# thermokoppel.net
KiCad netlist of a schematic drawn in Altium Designer
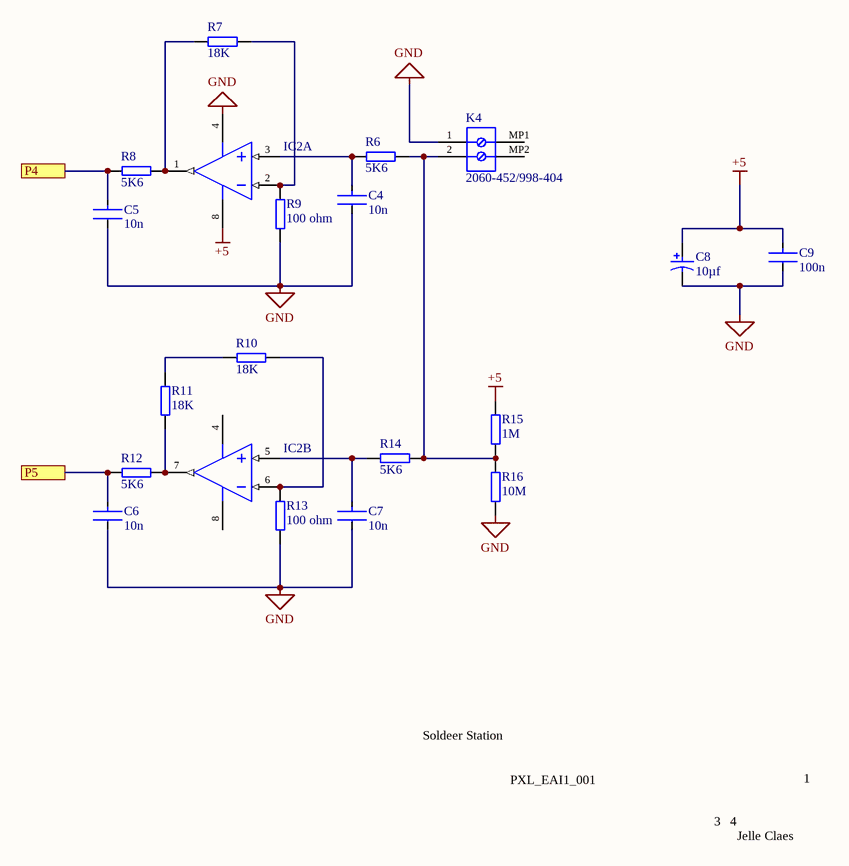
[diagram p0: thermokoppel.SchDoc]

(export (version "E")
  (design (tool "Eeschema 10.0.6"))
  (components
    (comp (ref "C4")
      (value "10n")
      (footprint "CC_0805_m")
      (fields
        (field (name "MANUFACTURER") "KEMET")
        (field (name "OCTOPART") "https://octopart.com/c0805c224k5ractu-kemet-144670")
        (field (name "MANUFACTURER PART NUMBER") "C0805C224K5RACTU")
      )
      (libsource (lib "soldeerstation") (part "Capacitor_Ceramic"))
    )
    (comp (ref "C5")
      (value "10n")
      (footprint "CC_0805_m")
      (fields
        (field (name "MANUFACTURER") "KEMET")
        (field (name "OCTOPART") "https://octopart.com/c0805c224k5ractu-kemet-144670")
        (field (name "MANUFACTURER PART NUMBER") "C0805C224K5RACTU")
      )
      (libsource (lib "soldeerstation") (part "Capacitor_Ceramic"))
    )
    (comp (ref "C6")
      (value "10n")
      (footprint "CC_0805_m")
      (fields
        (field (name "MANUFACTURER") "KEMET")
        (field (name "OCTOPART") "https://octopart.com/c0805c224k5ractu-kemet-144670")
        (field (name "MANUFACTURER PART NUMBER") "C0805C224K5RACTU")
      )
      (libsource (lib "soldeerstation") (part "Capacitor_Ceramic"))
    )
    (comp (ref "C7")
      (value "10n")
      (footprint "CC_0805_m")
      (fields
        (field (name "MANUFACTURER") "KEMET")
        (field (name "OCTOPART") "https://octopart.com/c0805c224k5ractu-kemet-144670")
        (field (name "MANUFACTURER PART NUMBER") "C0805C224K5RACTU")
      )
      (libsource (lib "soldeerstation") (part "Capacitor_Ceramic"))
    )
    (comp (ref "C8")
      (value "10µf")
      (footprint "CE_D8_L10")
      (fields (field (name "MANUFACTURER") "Panasonic"))
      (libsource (lib "soldeerstation") (part "Capacitor_Electrolytic"))
    )
    (comp (ref "C9")
      (value "100n")
      (footprint "CC_0805_m")
      (fields
        (field (name "MANUFACTURER") "KEMET")
        (field (name "OCTOPART") "https://octopart.com/c0805c224k5ractu-kemet-144670")
        (field (name "MANUFACTURER PART NUMBER") "C0805C224K5RACTU")
      )
      (libsource (lib "soldeerstation") (part "Capacitor_Ceramic"))
    )
    (comp (ref "IC2")
      (value "Dual_Opamp")
      (footprint "MSOP_8_M")
      (libsource (lib "soldeerstation") (part "Dual_Opamp"))
    )
    (comp (ref "K4")
      (value "2060-452/998-404")
      (footprint "WAGO-2060-452_V")
      (description "Terminal Block, Pitch 4 mm, 1 x 2 Position, Height 4.5 mm, -60 to 105 degC, RoHS, Tape and Reel")
      (fields (field (name "MANUFACTURER") "WAGO"))
      (libsource (lib "soldeerstation") (part "WAGO-2060"))
    )
    (comp (ref "R6")
      (value "5K6")
      (footprint "R_0805_M")
      (fields (field (name "MANUFACTURER") "Vishay Dale") (field (name "PART NUMBER") "CRCW08050000Z0EA"))
      (libsource (lib "soldeerstation") (part "Resistor"))
    )
    (comp (ref "R7")
      (value "18K")
      (footprint "R_0805_M")
      (fields (field (name "MANUFACTURER") "Vishay Dale") (field (name "PART NUMBER") "CRCW08050000Z0EA"))
      (libsource (lib "soldeerstation") (part "Resistor"))
    )
    (comp (ref "R8")
      (value "5K6")
      (footprint "R_0805_M")
      (fields (field (name "MANUFACTURER") "Vishay Dale") (field (name "PART NUMBER") "CRCW08050000Z0EA"))
      (libsource (lib "soldeerstation") (part "Resistor"))
    )
    (comp (ref "R9")
      (value "100 ohm")
      (footprint "R_0805_M")
      (fields (field (name "MANUFACTURER") "Vishay Dale") (field (name "PART NUMBER") "CRCW08050000Z0EA"))
      (libsource (lib "soldeerstation") (part "Resistor"))
    )
    (comp (ref "R10")
      (value "18K")
      (footprint "R_0805_M")
      (fields (field (name "MANUFACTURER") "Vishay Dale") (field (name "PART NUMBER") "CRCW08050000Z0EA"))
      (libsource (lib "soldeerstation") (part "Resistor"))
    )
    (comp (ref "R11")
      (value "18K")
      (footprint "R_0805_M")
      (fields (field (name "MANUFACTURER") "Vishay Dale") (field (name "PART NUMBER") "CRCW08050000Z0EA"))
      (libsource (lib "soldeerstation") (part "Resistor"))
    )
    (comp (ref "R12")
      (value "5K6")
      (footprint "R_0805_M")
      (fields (field (name "MANUFACTURER") "Vishay Dale") (field (name "PART NUMBER") "CRCW08050000Z0EA"))
      (libsource (lib "soldeerstation") (part "Resistor"))
    )
    (comp (ref "R13")
      (value "100 ohm")
      (footprint "R_0805_M")
      (fields (field (name "MANUFACTURER") "Vishay Dale") (field (name "PART NUMBER") "CRCW08050000Z0EA"))
      (libsource (lib "soldeerstation") (part "Resistor"))
    )
    (comp (ref "R14")
      (value "5K6")
      (footprint "R_0805_M")
      (fields (field (name "MANUFACTURER") "Vishay Dale") (field (name "PART NUMBER") "CRCW08050000Z0EA"))
      (libsource (lib "soldeerstation") (part "Resistor"))
    )
    (comp (ref "R15")
      (value "1M")
      (footprint "R_0805_M")
      (fields (field (name "MANUFACTURER") "Vishay Dale") (field (name "PART NUMBER") "CRCW08050000Z0EA"))
      (libsource (lib "soldeerstation") (part "Resistor"))
    )
    (comp (ref "R16")
      (value "10M")
      (footprint "R_0805_M")
      (fields (field (name "MANUFACTURER") "Vishay Dale") (field (name "PART NUMBER") "CRCW08050000Z0EA"))
      (libsource (lib "soldeerstation") (part "Resistor"))
    )
  )
  (nets
    (net (code "1") (name "+5") (class "Default")
      (node (ref "C8") (pin "2") (pinfunction "2_2") (pintype "passive"))
      (node (ref "C9") (pin "1") (pinfunction "1_1") (pintype "passive"))
      (node (ref "IC2") (pin "8") (pinfunction "VDD_8") (pintype "power_in"))
      (node (ref "R15") (pin "2") (pinfunction "2_2") (pintype "passive"))
    )
    (net (code "2") (name "/P4") (class "Default")
      (node (ref "C5") (pin "1") (pinfunction "1_1") (pintype "passive"))
      (node (ref "R8") (pin "1") (pinfunction "1_1") (pintype "passive"))
    )
    (net (code "3") (name "/P5") (class "Default")
      (node (ref "C6") (pin "1") (pinfunction "1_1") (pintype "passive"))
      (node (ref "R12") (pin "2") (pinfunction "2_2") (pintype "passive"))
    )
    (net (code "4") (name "GND") (class "Default")
      (node (ref "C4") (pin "2") (pinfunction "2_2") (pintype "passive"))
      (node (ref "C5") (pin "2") (pinfunction "2_2") (pintype "passive"))
      (node (ref "C6") (pin "2") (pinfunction "2_2") (pintype "passive"))
      (node (ref "C7") (pin "2") (pinfunction "2_2") (pintype "passive"))
      (node (ref "C8") (pin "1") (pinfunction "1_1") (pintype "passive"))
      (node (ref "C9") (pin "2") (pinfunction "2_2") (pintype "passive"))
      (node (ref "IC2") (pin "4") (pinfunction "VSS_4") (pintype "power_in"))
      (node (ref "K4") (pin "1") (pinfunction "1_1") (pintype "passive"))
      (node (ref "R13") (pin "2") (pinfunction "2_2") (pintype "passive"))
      (node (ref "R16") (pin "1") (pinfunction "1_1") (pintype "passive"))
      (node (ref "R9") (pin "2") (pinfunction "2_2") (pintype "passive"))
    )
    (net (code "5") (name "Net-(IC2A-VINA+)") (class "Default")
      (node (ref "C4") (pin "1") (pinfunction "1_1") (pintype "passive"))
      (node (ref "IC2") (pin "3") (pinfunction "VINA+_3") (pintype "input"))
      (node (ref "R6") (pin "1") (pinfunction "1_1") (pintype "passive"))
    )
    (net (code "6") (name "Net-(IC2A-VINA-)") (class "Default")
      (node (ref "IC2") (pin "2") (pinfunction "VINA-_2") (pintype "input"))
      (node (ref "R7") (pin "2") (pinfunction "2_2") (pintype "passive"))
      (node (ref "R9") (pin "1") (pinfunction "1_1") (pintype "passive"))
    )
    (net (code "7") (name "Net-(IC2A-VOUTA)") (class "Default")
      (node (ref "IC2") (pin "1") (pinfunction "VOUTA_1") (pintype "output"))
      (node (ref "R7") (pin "1") (pinfunction "1_1") (pintype "passive"))
      (node (ref "R8") (pin "2") (pinfunction "2_2") (pintype "passive"))
    )
    (net (code "8") (name "Net-(IC2B-VINB+)") (class "Default")
      (node (ref "C7") (pin "1") (pinfunction "1_1") (pintype "passive"))
      (node (ref "IC2") (pin "5") (pinfunction "VINB+_5") (pintype "input"))
      (node (ref "R14") (pin "1") (pinfunction "1_1") (pintype "passive"))
    )
    (net (code "9") (name "Net-(IC2B-VINB-)") (class "Default")
      (node (ref "IC2") (pin "6") (pinfunction "VINB-_6") (pintype "input"))
      (node (ref "R10") (pin "2") (pinfunction "2_2") (pintype "passive"))
      (node (ref "R13") (pin "1") (pinfunction "1_1") (pintype "passive"))
    )
    (net (code "10") (name "Net-(IC2B-VOUTB)") (class "Default")
      (node (ref "IC2") (pin "7") (pinfunction "VOUTB_7") (pintype "output"))
      (node (ref "R11") (pin "1") (pinfunction "1_1") (pintype "passive"))
      (node (ref "R12") (pin "1") (pinfunction "1_1") (pintype "passive"))
    )
    (net (code "11") (name "Net-(K4-Pad2)") (class "Default")
      (node (ref "K4") (pin "2") (pinfunction "2_2") (pintype "passive"))
      (node (ref "R14") (pin "2") (pinfunction "2_2") (pintype "passive"))
      (node (ref "R15") (pin "1") (pinfunction "1_1") (pintype "passive"))
      (node (ref "R16") (pin "2") (pinfunction "2_2") (pintype "passive"))
      (node (ref "R6") (pin "2") (pinfunction "2_2") (pintype "passive"))
    )
    (net (code "12") (name "Net-(R10-Pad1)") (class "Default")
      (node (ref "R10") (pin "1") (pinfunction "1_1") (pintype "passive"))
      (node (ref "R11") (pin "2") (pinfunction "2_2") (pintype "passive"))
    )
    (net (code "13") (name "unconnected-(IC2B-VDD-Pad8)") (class "Default")
      (node (ref "IC2") (pin "8") (pinfunction "VDD_8") (pintype "power_in"))
    )
    (net (code "14") (name "unconnected-(IC2B-VSS-Pad4)") (class "Default")
      (node (ref "IC2") (pin "4") (pinfunction "VSS_4") (pintype "power_in"))
    )
    (net (code "15") (name "unconnected-(K4-PadMP1)") (class "Default")
      (node (ref "K4") (pin "MP1") (pinfunction "MP1_MP1") (pintype "passive"))
    )
    (net (code "16") (name "unconnected-(K4-PadMP2)") (class "Default")
      (node (ref "K4") (pin "MP2") (pinfunction "MP2_MP2") (pintype "passive"))
    )
  )
)
